# DVT-Atlas-Driver.net
KiCad netlist of a schematic drawn in Altium Designer
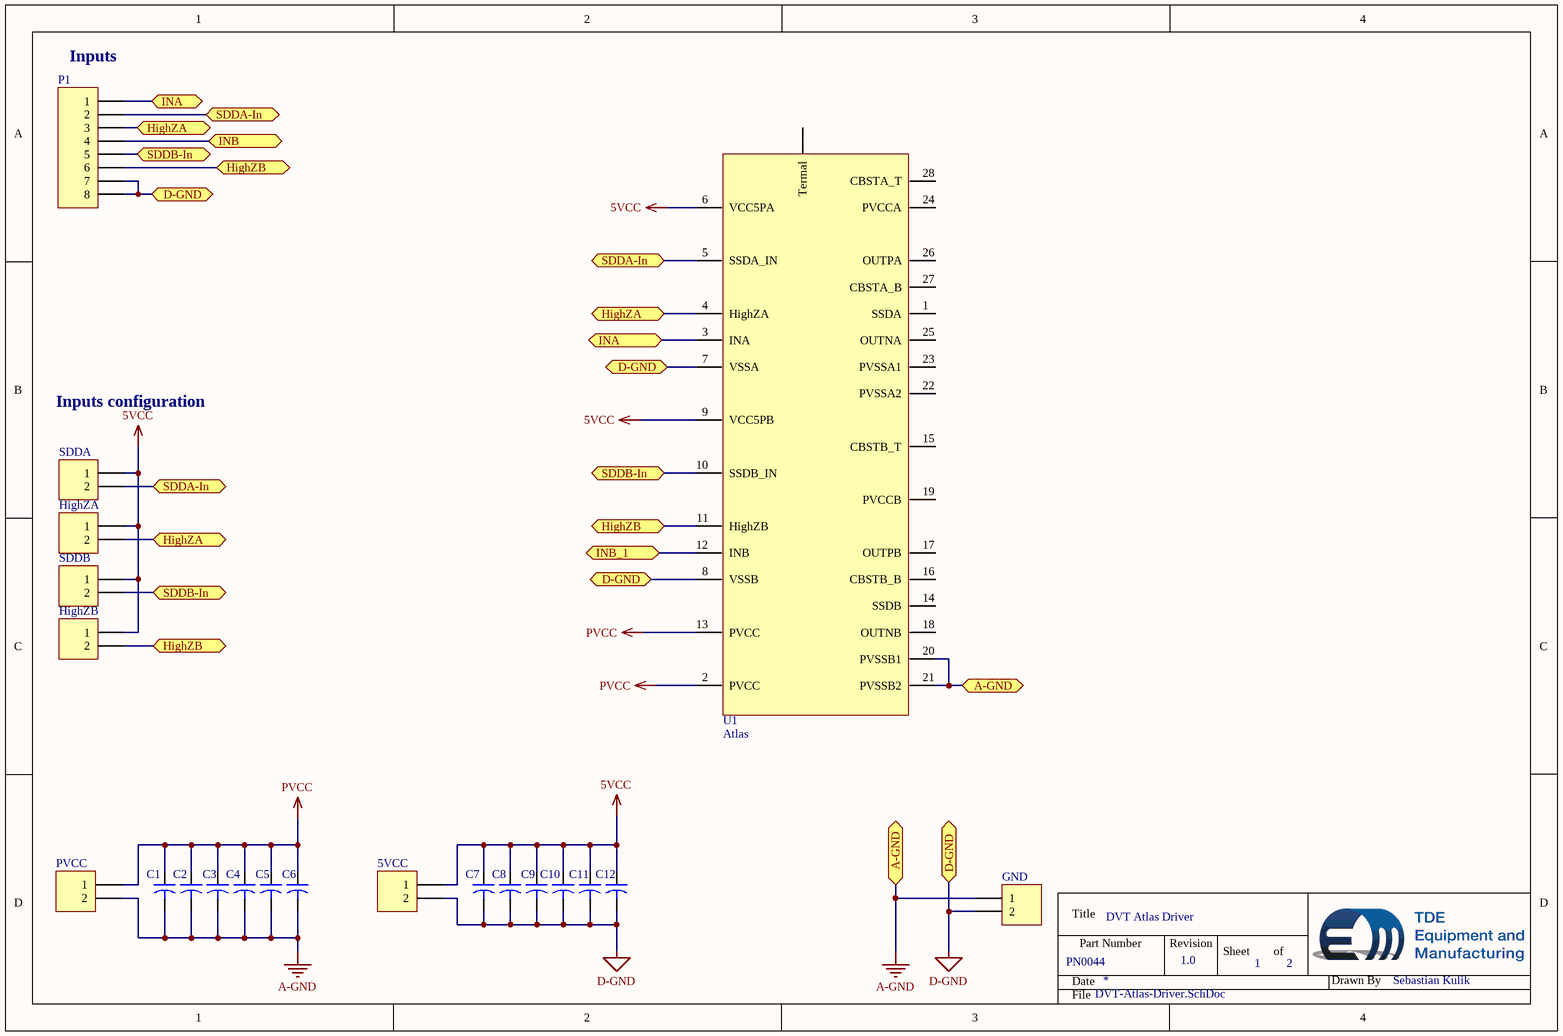
[diagram p0: DVT-Atlas-Driver.SchDoc]

(export (version "E")
  (design (tool "Eeschema 10.0.6"))
  (components
    (comp (ref "5VCC")
      (value "PHOENIX_1715721")
      (footprint "Phoenix-2-5_08")
      (description "Phoenix, 2 pol, 5.08mm, 22A, 715721")
      (fields (field (name "MANUFACTURER") "Phoenix") (field (name "PUBLISHER") "Sebastian Kulik"))
      (libsource (lib "Connectors") (part "2Pol_1715721"))
    )
    (comp (ref "C1")
      (value "Capacitor-Dummy-THT")
      (footprint "Dummy-10mm")
      (fields (field (name "PUBLISHER") "Sebastian Kulik"))
      (libsource (lib "Capacitors") (part "Capacitor-Dummy-THT"))
    )
    (comp (ref "C2")
      (value "Capacitor-Dummy-THT")
      (footprint "Dummy-10mm")
      (fields (field (name "PUBLISHER") "Sebastian Kulik"))
      (libsource (lib "Capacitors") (part "Capacitor-Dummy-THT"))
    )
    (comp (ref "C3")
      (value "Capacitor-Dummy-THT")
      (footprint "Dummy-10mm")
      (fields (field (name "PUBLISHER") "Sebastian Kulik"))
      (libsource (lib "Capacitors") (part "Capacitor-Dummy-THT"))
    )
    (comp (ref "C4")
      (value "Capacitor-Dummy-THT")
      (footprint "Dummy-10mm")
      (fields (field (name "PUBLISHER") "Sebastian Kulik"))
      (libsource (lib "Capacitors") (part "Capacitor-Dummy-THT"))
    )
    (comp (ref "C5")
      (value "Capacitor-Dummy-THT")
      (footprint "Dummy-10mm")
      (fields (field (name "PUBLISHER") "Sebastian Kulik"))
      (libsource (lib "Capacitors") (part "Capacitor-Dummy-THT"))
    )
    (comp (ref "C6")
      (value "Capacitor-Dummy-THT")
      (footprint "Dummy-10mm")
      (fields (field (name "PUBLISHER") "Sebastian Kulik"))
      (libsource (lib "Capacitors") (part "Capacitor-Dummy-THT"))
    )
    (comp (ref "C7")
      (value "Capacitor-Dummy-THT")
      (footprint "Dummy-10mm")
      (fields (field (name "PUBLISHER") "Sebastian Kulik"))
      (libsource (lib "Capacitors") (part "Capacitor-Dummy-THT"))
    )
    (comp (ref "C8")
      (value "Capacitor-Dummy-THT")
      (footprint "Dummy-10mm")
      (fields (field (name "PUBLISHER") "Sebastian Kulik"))
      (libsource (lib "Capacitors") (part "Capacitor-Dummy-THT"))
    )
    (comp (ref "C9")
      (value "Capacitor-Dummy-THT")
      (footprint "Dummy-10mm")
      (fields (field (name "PUBLISHER") "Sebastian Kulik"))
      (libsource (lib "Capacitors") (part "Capacitor-Dummy-THT"))
    )
    (comp (ref "C10")
      (value "Capacitor-Dummy-THT")
      (footprint "Dummy-10mm")
      (fields (field (name "PUBLISHER") "Sebastian Kulik"))
      (libsource (lib "Capacitors") (part "Capacitor-Dummy-THT"))
    )
    (comp (ref "C11")
      (value "Capacitor-Dummy-THT")
      (footprint "Dummy-10mm")
      (fields (field (name "PUBLISHER") "Sebastian Kulik"))
      (libsource (lib "Capacitors") (part "Capacitor-Dummy-THT"))
    )
    (comp (ref "C12")
      (value "Capacitor-Dummy-THT")
      (footprint "Dummy-10mm")
      (fields (field (name "PUBLISHER") "Sebastian Kulik"))
      (libsource (lib "Capacitors") (part "Capacitor-Dummy-THT"))
    )
    (comp (ref "GND")
      (value "PHOENIX_1715721")
      (footprint "Phoenix-2-5_08")
      (description "Phoenix, 2 pol, 5.08mm, 22A, 715721")
      (fields (field (name "MANUFACTURER") "Phoenix") (field (name "PUBLISHER") "Sebastian Kulik"))
      (libsource (lib "") (part "2Pol_1715721_1"))
    )
    (comp (ref "HighZA")
      (value "Plug_2_180_2.54")
      (footprint "HDR1X2")
      (description "Plug, 2-Pin")
      (fields (field (name "MANUFACTURER") "WE") (field (name "PUBLISHER") "Sebastian Kulik"))
      (libsource (lib "Connectors") (part "Plug_2_180_2.54"))
    )
    (comp (ref "HighZB")
      (value "Plug_2_180_2.54")
      (footprint "HDR1X2")
      (description "Plug, 2-Pin")
      (fields (field (name "MANUFACTURER") "WE") (field (name "PUBLISHER") "Sebastian Kulik"))
      (libsource (lib "Connectors") (part "Plug_2_180_2.54"))
    )
    (comp (ref "P1")
      (value "Plug_08_2.54")
      (footprint "HDR1X8_2.54")
      (description "Plug, 08-Pin")
      (fields (field (name "MANUFACTURER") "WE") (field (name "PUBLISHER") "Sebastian Kulik"))
      (libsource (lib "Connectors") (part "Plug_08_2.54"))
    )
    (comp (ref "PVCC")
      (value "PHOENIX_1715721")
      (footprint "Phoenix-2-5_08")
      (description "Phoenix, 2 pol, 5.08mm, 22A, 715721")
      (fields (field (name "MANUFACTURER") "Phoenix") (field (name "PUBLISHER") "Sebastian Kulik"))
      (libsource (lib "Connectors") (part "2Pol_1715721"))
    )
    (comp (ref "SDDA")
      (value "Plug_2_180_2.54")
      (footprint "HDR1X2")
      (description "Plug, 2-Pin")
      (fields (field (name "MANUFACTURER") "WE") (field (name "PUBLISHER") "Sebastian Kulik"))
      (libsource (lib "Connectors") (part "Plug_2_180_2.54"))
    )
    (comp (ref "SDDB")
      (value "Plug_2_180_2.54")
      (footprint "HDR1X2")
      (description "Plug, 2-Pin")
      (fields (field (name "MANUFACTURER") "WE") (field (name "PUBLISHER") "Sebastian Kulik"))
      (libsource (lib "Connectors") (part "Plug_2_180_2.54"))
    )
    (comp (ref "U1")
      (value "Atlas")
      (footprint "SOIC28")
      (description "Gate driver, 30V, HT")
      (fields (field (name "MANUFACTURER") "CISSOID") (field (name "PUBLISHER") "Sebastian Kulik"))
      (libsource (lib "ICs") (part "CHT_TIT3345E_CSOIC28_T"))
    )
  )
  (nets
    (net (code "1") (name "/HighZA") (class "Default")
      (node (ref "HighZA") (pin "2") (pinfunction "2_2") (pintype "passive"))
      (node (ref "P1") (pin "3") (pinfunction "3_3") (pintype "passive"))
      (node (ref "U1") (pin "4") (pinfunction "HighZA_4") (pintype "passive"))
    )
    (net (code "2") (name "/HighZB") (class "Default")
      (node (ref "HighZB") (pin "2") (pinfunction "2_2") (pintype "passive"))
      (node (ref "P1") (pin "6") (pinfunction "6_6") (pintype "passive"))
      (node (ref "U1") (pin "11") (pinfunction "HighZB_11") (pintype "passive"))
    )
    (net (code "3") (name "/INA") (class "Default")
      (node (ref "P1") (pin "1") (pinfunction "1_1") (pintype "passive"))
      (node (ref "U1") (pin "3") (pinfunction "INA_3") (pintype "passive"))
    )
    (net (code "4") (name "/INB") (class "Default")
      (node (ref "P1") (pin "4") (pinfunction "4_4") (pintype "passive"))
    )
    (net (code "5") (name "/INB_1") (class "Default")
      (node (ref "U1") (pin "12") (pinfunction "INB_12") (pintype "passive"))
    )
    (net (code "6") (name "/SDDA-In") (class "Default")
      (node (ref "P1") (pin "2") (pinfunction "2_2") (pintype "passive"))
      (node (ref "SDDA") (pin "2") (pinfunction "2_2") (pintype "passive"))
      (node (ref "U1") (pin "5") (pinfunction "SSDA_IN_5") (pintype "passive"))
    )
    (net (code "7") (name "/SDDB-In") (class "Default")
      (node (ref "P1") (pin "5") (pinfunction "5_5") (pintype "passive"))
      (node (ref "SDDB") (pin "2") (pinfunction "2_2") (pintype "passive"))
      (node (ref "U1") (pin "10") (pinfunction "SSDB_IN_10") (pintype "passive"))
    )
    (net (code "8") (name "5VCC") (class "Default")
      (node (ref "5VCC") (pin "1") (pinfunction "1_1") (pintype "passive"))
      (node (ref "C10") (pin "1") (pinfunction "1_1") (pintype "passive"))
      (node (ref "C11") (pin "1") (pinfunction "1_1") (pintype "passive"))
      (node (ref "C12") (pin "1") (pinfunction "1_1") (pintype "passive"))
      (node (ref "C7") (pin "1") (pinfunction "1_1") (pintype "passive"))
      (node (ref "C8") (pin "1") (pinfunction "1_1") (pintype "passive"))
      (node (ref "C9") (pin "1") (pinfunction "1_1") (pintype "passive"))
      (node (ref "HighZA") (pin "1") (pinfunction "1_1") (pintype "passive"))
      (node (ref "HighZB") (pin "1") (pinfunction "1_1") (pintype "passive"))
      (node (ref "SDDA") (pin "1") (pinfunction "1_1") (pintype "passive"))
      (node (ref "SDDB") (pin "1") (pinfunction "1_1") (pintype "passive"))
      (node (ref "U1") (pin "6") (pinfunction "VCC5PA_6") (pintype "passive"))
      (node (ref "U1") (pin "9") (pinfunction "VCC5PB_9") (pintype "passive"))
    )
    (net (code "9") (name "A-GND") (class "Default")
      (node (ref "C1") (pin "2") (pinfunction "2_2") (pintype "passive"))
      (node (ref "C2") (pin "2") (pinfunction "2_2") (pintype "passive"))
      (node (ref "C3") (pin "2") (pinfunction "2_2") (pintype "passive"))
      (node (ref "C4") (pin "2") (pinfunction "2_2") (pintype "passive"))
      (node (ref "C5") (pin "2") (pinfunction "2_2") (pintype "passive"))
      (node (ref "C6") (pin "2") (pinfunction "2_2") (pintype "passive"))
      (node (ref "GND") (pin "1") (pinfunction "1_1") (pintype "passive"))
      (node (ref "PVCC") (pin "2") (pinfunction "2_2") (pintype "passive"))
      (node (ref "U1") (pin "20") (pinfunction "PVSSB1_20") (pintype "power_in"))
      (node (ref "U1") (pin "21") (pinfunction "PVSSB2_21") (pintype "passive"))
    )
    (net (code "10") (name "D-GND") (class "Default")
      (node (ref "5VCC") (pin "2") (pinfunction "2_2") (pintype "passive"))
      (node (ref "C10") (pin "2") (pinfunction "2_2") (pintype "passive"))
      (node (ref "C11") (pin "2") (pinfunction "2_2") (pintype "passive"))
      (node (ref "C12") (pin "2") (pinfunction "2_2") (pintype "passive"))
      (node (ref "C7") (pin "2") (pinfunction "2_2") (pintype "passive"))
      (node (ref "C8") (pin "2") (pinfunction "2_2") (pintype "passive"))
      (node (ref "C9") (pin "2") (pinfunction "2_2") (pintype "passive"))
      (node (ref "GND") (pin "2") (pinfunction "2_2") (pintype "passive"))
      (node (ref "P1") (pin "7") (pinfunction "7_7") (pintype "passive"))
      (node (ref "P1") (pin "8") (pinfunction "8_8") (pintype "passive"))
      (node (ref "U1") (pin "7") (pinfunction "VSSA_7") (pintype "passive"))
      (node (ref "U1") (pin "8") (pinfunction "VSSB_8") (pintype "passive"))
    )
    (net (code "11") (name "PVCC") (class "Default")
      (node (ref "C1") (pin "1") (pinfunction "1_1") (pintype "passive"))
      (node (ref "C2") (pin "1") (pinfunction "1_1") (pintype "passive"))
      (node (ref "C3") (pin "1") (pinfunction "1_1") (pintype "passive"))
      (node (ref "C4") (pin "1") (pinfunction "1_1") (pintype "passive"))
      (node (ref "C5") (pin "1") (pinfunction "1_1") (pintype "passive"))
      (node (ref "C6") (pin "1") (pinfunction "1_1") (pintype "passive"))
      (node (ref "PVCC") (pin "1") (pinfunction "1_1") (pintype "passive"))
      (node (ref "U1") (pin "13") (pinfunction "PVCC_13") (pintype "passive"))
      (node (ref "U1") (pin "2") (pinfunction "PVCC_2") (pintype "passive"))
    )
    (net (code "12") (name "unconnected-(U1-CBSTA_B-Pad27)") (class "Default")
      (node (ref "U1") (pin "27") (pinfunction "CBSTA_B_27") (pintype "passive"))
    )
    (net (code "13") (name "unconnected-(U1-CBSTA_T-Pad28)") (class "Default")
      (node (ref "U1") (pin "28") (pinfunction "CBSTA_T_28") (pintype "power_in"))
    )
    (net (code "14") (name "unconnected-(U1-CBSTB_B-Pad16)") (class "Default")
      (node (ref "U1") (pin "16") (pinfunction "CBSTB_B_16") (pintype "passive"))
    )
    (net (code "15") (name "unconnected-(U1-CBSTB_T-Pad15)") (class "Default")
      (node (ref "U1") (pin "15") (pinfunction "CBSTB_T_15") (pintype "passive"))
    )
    (net (code "16") (name "unconnected-(U1-OUTNA-Pad25)") (class "Default")
      (node (ref "U1") (pin "25") (pinfunction "OUTNA_25") (pintype "passive"))
    )
    (net (code "17") (name "unconnected-(U1-OUTNB-Pad18)") (class "Default")
      (node (ref "U1") (pin "18") (pinfunction "OUTNB_18") (pintype "passive"))
    )
    (net (code "18") (name "unconnected-(U1-OUTPA-Pad26)") (class "Default")
      (node (ref "U1") (pin "26") (pinfunction "OUTPA_26") (pintype "power_in"))
    )
    (net (code "19") (name "unconnected-(U1-OUTPB-Pad17)") (class "Default")
      (node (ref "U1") (pin "17") (pinfunction "OUTPB_17") (pintype "power_in"))
    )
    (net (code "20") (name "unconnected-(U1-PVCCA-Pad24)") (class "Default")
      (node (ref "U1") (pin "24") (pinfunction "PVCCA_24") (pintype "passive"))
    )
    (net (code "21") (name "unconnected-(U1-PVCCB-Pad19)") (class "Default")
      (node (ref "U1") (pin "19") (pinfunction "PVCCB_19") (pintype "passive"))
    )
    (net (code "22") (name "unconnected-(U1-PVSSA1-Pad23)") (class "Default")
      (node (ref "U1") (pin "23") (pinfunction "PVSSA1_23") (pintype "power_in"))
    )
    (net (code "23") (name "unconnected-(U1-PVSSA2-Pad22)") (class "Default")
      (node (ref "U1") (pin "22") (pinfunction "PVSSA2_22") (pintype "passive"))
    )
    (net (code "24") (name "unconnected-(U1-SSDA-Pad1)") (class "Default")
      (node (ref "U1") (pin "1") (pinfunction "SSDA_1") (pintype "power_in"))
    )
    (net (code "25") (name "unconnected-(U1-SSDB-Pad14)") (class "Default")
      (node (ref "U1") (pin "14") (pinfunction "SSDB_14") (pintype "power_in"))
    )
    (net (code "26") (name "unconnected-(U1-Termal-Pad29)") (class "Default")
      (node (ref "U1") (pin "29") (pinfunction "Termal_29") (pintype "passive"))
    )
  )
)
